# RFID.net
KiCad netlist of a schematic drawn in Altium Designer
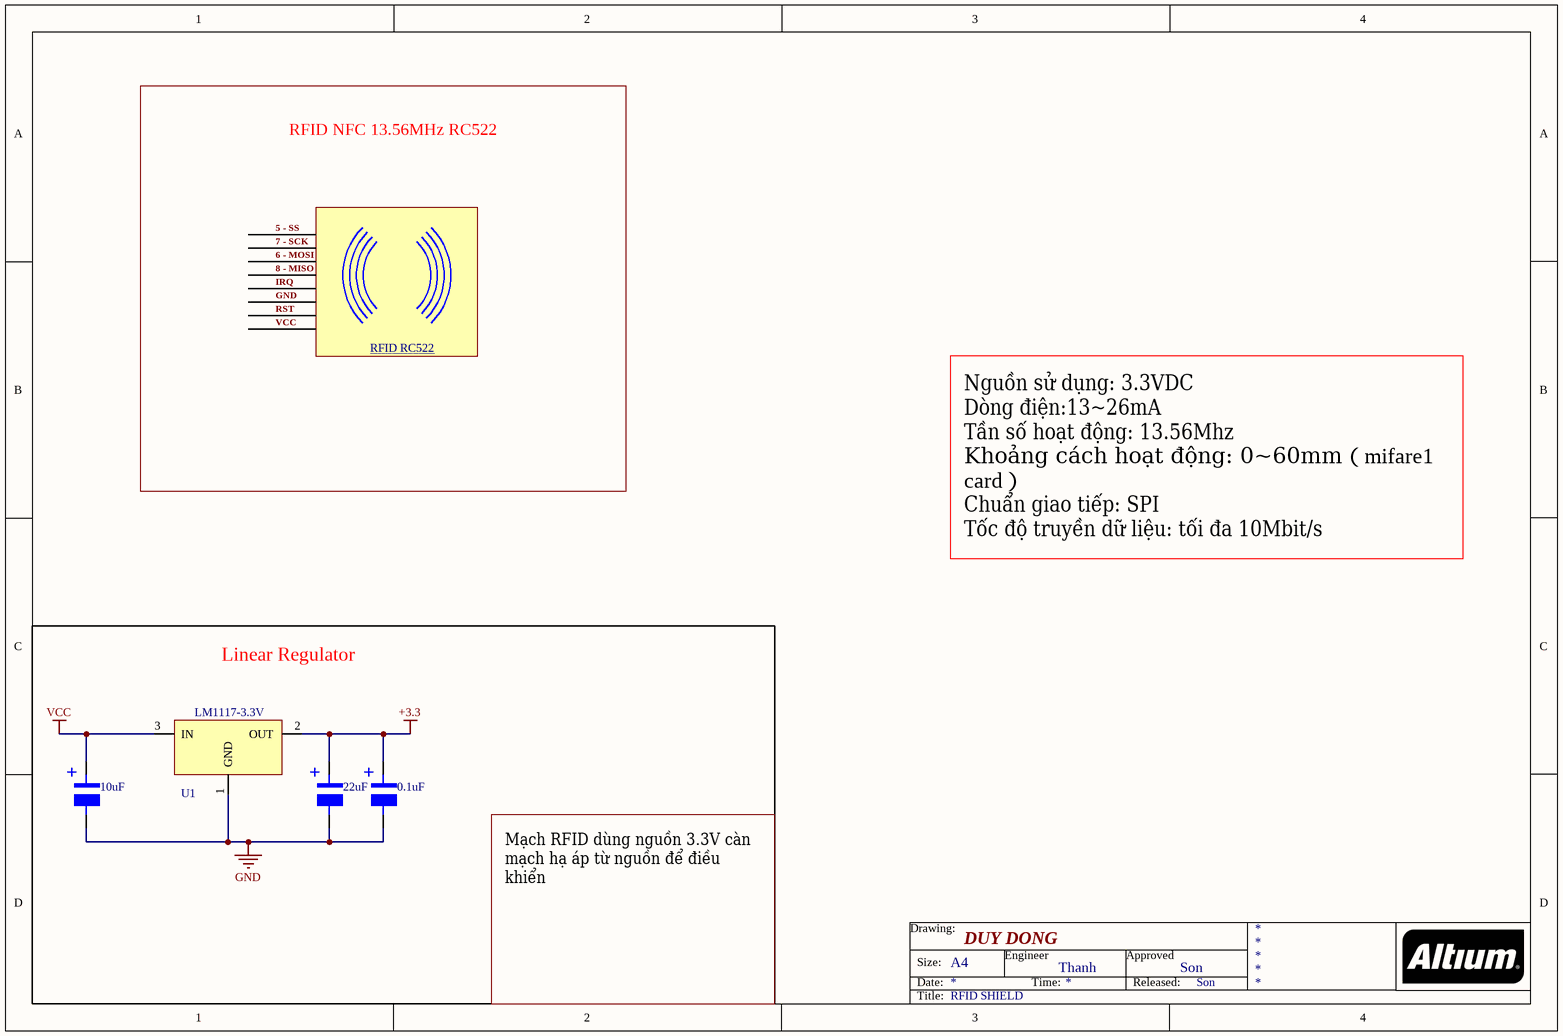
[diagram p0: RFID.SchDoc]

(export (version "E")
  (design (tool "Eeschema 10.0.6"))
  (components
    (comp (ref "C1") (value "10uF") (footprint "Cty1:Cap220uF") (libsource (lib "Cty1") (part "Cap220uF")))
    (comp (ref "C2") (value "22uF") (footprint "Cty1:Cap220uF") (libsource (lib "Cty1") (part "Cap220uF")))
    (comp (ref "C3") (value "0.1uF") (footprint "Cty1:Cap220uF") (libsource (lib "Cty1") (part "Cap220uF")))
    (comp (ref "U1")
      (value "LM1117-3.3V")
      (footprint "SOT223-4N")
      (description "800mA Low-Dropout Linear Regulator")
      (fields (field (name "CREATOR") "Nguyen Ba Bien"))
      (libsource (lib "Cty1") (part "LM1117"))
    )
  )
  (nets
    (net (code "1") (name "+3.3") (class "Default")
      (node (ref "C2") (pin "1") (pinfunction "1_1") (pintype "passive"))
      (node (ref "C3") (pin "1") (pinfunction "1_1") (pintype "passive"))
      (node (ref "U1") (pin "2") (pinfunction "OUT_2") (pintype "passive"))
    )
    (net (code "8") (name "GND") (class "Default")
      (node (ref "C1") (pin "2") (pinfunction "2_2") (pintype "passive"))
      (node (ref "C2") (pin "2") (pinfunction "2_2") (pintype "passive"))
      (node (ref "C3") (pin "2") (pinfunction "2_2") (pintype "passive"))
      (node (ref "U1") (pin "1") (pinfunction "GND_1") (pintype "passive"))
    )
    (net (code "9") (name "VCC") (class "Default")
      (node (ref "C1") (pin "1") (pinfunction "1_1") (pintype "passive"))
      (node (ref "U1") (pin "3") (pinfunction "IN_3") (pintype "passive"))
    )
  )
)
